# 3b_Motor_Interface.net
KiCad netlist of a schematic drawn in Altium Designer
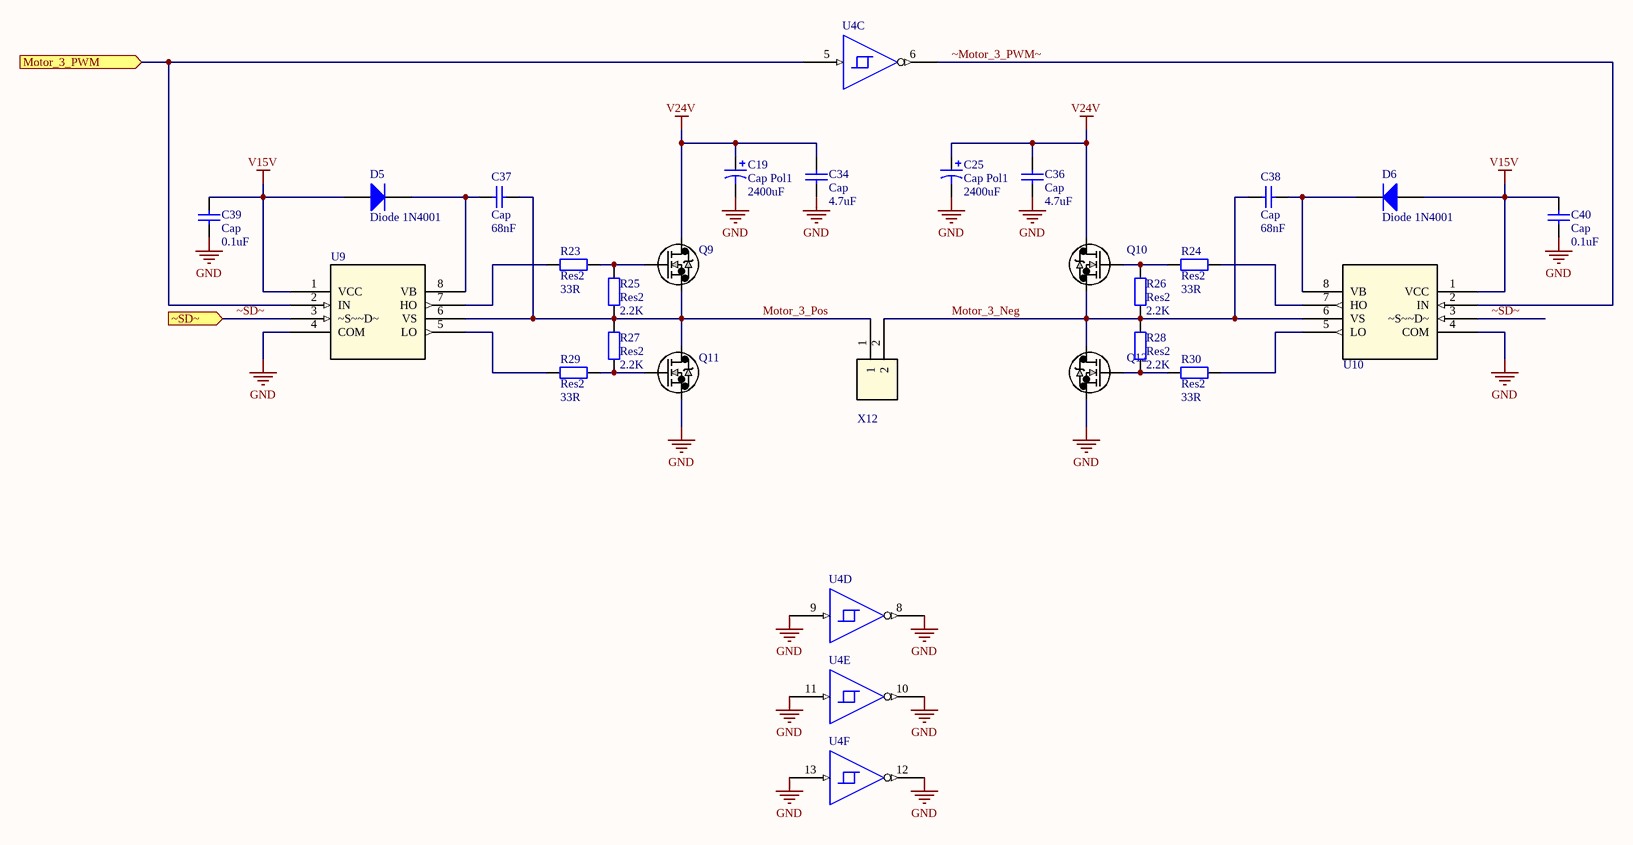
[diagram p0: 3b_Motor_Interface.SchDoc]

(export (version "E")
  (design (tool "Eeschema 10.0.6"))
  (components
    (comp (ref "C19")
      (value "Cap Pol1")
      (footprint "RB7.6-15")
      (description "Polarized Capacitor (Radial)")
      (fields (field (name "ALTIUM_VALUE") "2400uF") (field (name "PUBLISHER") "Altium Limited"))
      (libsource (lib "Miscellaneous Devices") (part "Cap Pol1"))
    )
    (comp (ref "C25")
      (value "Cap Pol1")
      (footprint "RB7.6-15")
      (description "Polarized Capacitor (Radial)")
      (fields (field (name "ALTIUM_VALUE") "2400uF") (field (name "PUBLISHER") "Altium Limited"))
      (libsource (lib "Miscellaneous Devices") (part "Cap Pol1"))
    )
    (comp (ref "C34")
      (value "Cap")
      (footprint "RAD-0.3")
      (description "Capacitor")
      (fields (field (name "ALTIUM_VALUE") "4.7uF") (field (name "PUBLISHER") "Altium Limited"))
      (libsource (lib "Miscellaneous Devices") (part "Cap"))
    )
    (comp (ref "C36")
      (value "Cap")
      (footprint "RAD-0.3")
      (description "Capacitor")
      (fields (field (name "ALTIUM_VALUE") "4.7uF") (field (name "PUBLISHER") "Altium Limited"))
      (libsource (lib "Miscellaneous Devices") (part "Cap"))
    )
    (comp (ref "C37")
      (value "Cap")
      (footprint "RAD-0.3")
      (description "Capacitor")
      (fields (field (name "ALTIUM_VALUE") "68nF") (field (name "PUBLISHER") "Altium Limited"))
      (libsource (lib "Miscellaneous Devices") (part "Cap"))
    )
    (comp (ref "C38")
      (value "Cap")
      (footprint "RAD-0.3")
      (description "Capacitor")
      (fields (field (name "ALTIUM_VALUE") "68nF") (field (name "PUBLISHER") "Altium Limited"))
      (libsource (lib "Miscellaneous Devices") (part "Cap"))
    )
    (comp (ref "C39")
      (value "Cap")
      (footprint "RAD-0.3")
      (description "Capacitor")
      (fields (field (name "ALTIUM_VALUE") "0.1uF") (field (name "PUBLISHER") "Altium Limited"))
      (libsource (lib "Miscellaneous Devices") (part "Cap"))
    )
    (comp (ref "C40")
      (value "Cap")
      (footprint "RAD-0.3")
      (description "Capacitor")
      (fields (field (name "ALTIUM_VALUE") "0.1uF") (field (name "PUBLISHER") "Altium Limited"))
      (libsource (lib "Miscellaneous Devices") (part "Cap"))
    )
    (comp (ref "D5")
      (value "Diode 1N4001")
      (footprint "DO-41")
      (description "1 Amp General Purpose Rectifier")
      (fields (field (name "PUBLISHER") "Altium Limited"))
      (libsource (lib "Miscellaneous Devices") (part "Diode 1N4001"))
    )
    (comp (ref "D6")
      (value "Diode 1N4001")
      (footprint "DO-41")
      (description "1 Amp General Purpose Rectifier")
      (fields (field (name "PUBLISHER") "Altium Limited"))
      (libsource (lib "Miscellaneous Devices") (part "Diode 1N4001"))
    )
    (comp (ref "Q9")
      (value "STP100N6F7")
      (footprint "thomas_lib:TO-220")
      (fields (field (name "DIGI-KEY_PART_NUMBER") "497-15888-5-ND"))
      (libsource (lib "thomas_lib") (part "STP100N6F7"))
    )
    (comp (ref "Q10")
      (value "STP100N6F7")
      (footprint "thomas_lib:TO-220")
      (fields (field (name "DIGI-KEY_PART_NUMBER") "497-15888-5-ND"))
      (libsource (lib "thomas_lib") (part "STP100N6F7"))
    )
    (comp (ref "Q11")
      (value "STP100N6F7")
      (footprint "thomas_lib:TO-220")
      (fields (field (name "DIGI-KEY_PART_NUMBER") "497-15888-5-ND"))
      (libsource (lib "thomas_lib") (part "STP100N6F7"))
    )
    (comp (ref "Q12")
      (value "STP100N6F7")
      (footprint "thomas_lib:TO-220")
      (fields (field (name "DIGI-KEY_PART_NUMBER") "497-15888-5-ND"))
      (libsource (lib "thomas_lib") (part "STP100N6F7"))
    )
    (comp (ref "R23")
      (value "Res2")
      (footprint "AXIAL-0.4")
      (description "Resistor")
      (fields (field (name "ALTIUM_VALUE") "33R") (field (name "PUBLISHER") "Altium Limited"))
      (libsource (lib "Miscellaneous Devices") (part "Res2"))
    )
    (comp (ref "R24")
      (value "Res2")
      (footprint "AXIAL-0.4")
      (description "Resistor")
      (fields (field (name "ALTIUM_VALUE") "33R") (field (name "PUBLISHER") "Altium Limited"))
      (libsource (lib "") (part "Res2_1"))
    )
    (comp (ref "R25")
      (value "Res2")
      (footprint "AXIAL-0.4")
      (description "Resistor")
      (fields (field (name "ALTIUM_VALUE") "2.2K") (field (name "PUBLISHER") "Altium Limited"))
      (libsource (lib "") (part "Res2_2"))
    )
    (comp (ref "R26")
      (value "Res2")
      (footprint "AXIAL-0.4")
      (description "Resistor")
      (fields (field (name "ALTIUM_VALUE") "2.2K") (field (name "PUBLISHER") "Altium Limited"))
      (libsource (lib "Miscellaneous Devices") (part "Res2"))
    )
    (comp (ref "R27")
      (value "Res2")
      (footprint "AXIAL-0.4")
      (description "Resistor")
      (fields (field (name "ALTIUM_VALUE") "2.2K") (field (name "PUBLISHER") "Altium Limited"))
      (libsource (lib "") (part "Res2_2"))
    )
    (comp (ref "R28")
      (value "Res2")
      (footprint "AXIAL-0.4")
      (description "Resistor")
      (fields (field (name "ALTIUM_VALUE") "2.2K") (field (name "PUBLISHER") "Altium Limited"))
      (libsource (lib "Miscellaneous Devices") (part "Res2"))
    )
    (comp (ref "R29")
      (value "Res2")
      (footprint "AXIAL-0.4")
      (description "Resistor")
      (fields (field (name "ALTIUM_VALUE") "33R") (field (name "PUBLISHER") "Altium Limited"))
      (libsource (lib "Miscellaneous Devices") (part "Res2"))
    )
    (comp (ref "R30")
      (value "Res2")
      (footprint "AXIAL-0.4")
      (description "Resistor")
      (fields (field (name "ALTIUM_VALUE") "33R") (field (name "PUBLISHER") "Altium Limited"))
      (libsource (lib "") (part "Res2_1"))
    )
    (comp (ref "U4")
      (value "IC HEX SCHMITT-TRIG INV 14-DIP")
      (footprint "14-DIP")
      (fields
        (field (name "DIGI-KEY_PART_NUMBER") "296-4368-5-ND")
        (field (name "MANUFACTUER_PART_NUMBER") "SN74ACT14N")
        (field (name "MANUFACTURER") "Texas Instruments")
      )
      (libsource (lib "thomas_lib") (part "IC HEX SCHMITT-TRIG INV 14-DIP"))
    )
    (comp (ref "U9")
      (value "IC DRIVER HALF BRIDGE 8DIP")
      (footprint "thomas_lib:8-DIP")
      (fields
        (field (name "MANUFACTURER_PART_NUMBER") "IR2109PBF")
        (field (name "DIGI-KEY_PART_NUMBER") "IR2109PBF-ND")
        (field (name "MANUFACTURER") "Infineon Technologies")
      )
      (libsource (lib "thomas_lib") (part "IC DRIVER HALF BRIDGE 8DIP"))
    )
    (comp (ref "U10")
      (value "IC DRIVER HALF BRIDGE 8DIP")
      (footprint "thomas_lib:8-DIP")
      (fields
        (field (name "MANUFACTURER_PART_NUMBER") "IR2109PBF")
        (field (name "DIGI-KEY_PART_NUMBER") "IR2109PBF-ND")
        (field (name "MANUFACTURER") "Infineon Technologies")
      )
      (libsource (lib "") (part "IC DRIVER HALF BRIDGE 8DIP_1"))
    )
    (comp (ref "X12")
      (value "TERM BLOCK HDR 2POS VERT 3.5MM")
      (footprint "WR-TBL-3211 2")
      (fields
        (field (name "DIGIKEY_PART_NUMBER") "732-2763-ND")
        (field (name "MANUFACTURER_PART_NUMBER") "691321100002")
        (field (name "MANUFACTURER") "Wurth Electronics Inc")
      )
      (libsource (lib "thomas_lib") (part "TERM BLOCK HDR 2POS VERT 3.5MM"))
    )
  )
  (nets
    (net (code "1") (name "/Motor_3_Neg") (class "Default")
      (node (ref "C38") (pin "1") (pinfunction "1_1") (pintype "passive"))
      (node (ref "Q10") (pin "3") (pinfunction "3_3") (pintype "passive"))
      (node (ref "Q12") (pin "2") (pinfunction "2_2") (pintype "passive"))
      (node (ref "R26") (pin "2") (pinfunction "2_2") (pintype "passive"))
      (node (ref "R28") (pin "1") (pinfunction "1_1") (pintype "passive"))
      (node (ref "U10") (pin "6") (pinfunction "VS_6") (pintype "power_in"))
      (node (ref "X12") (pin "2") (pinfunction "2_2") (pintype "passive"))
    )
    (net (code "2") (name "/Motor_3_PWM") (class "Default")
      (node (ref "U4") (pin "5") (pinfunction "A_5") (pintype "input"))
      (node (ref "U9") (pin "2") (pinfunction "IN_2") (pintype "input"))
    )
    (net (code "3") (name "/Motor_3_Pos") (class "Default")
      (node (ref "C37") (pin "1") (pinfunction "1_1") (pintype "passive"))
      (node (ref "Q11") (pin "2") (pinfunction "2_2") (pintype "passive"))
      (node (ref "Q9") (pin "3") (pinfunction "3_3") (pintype "passive"))
      (node (ref "R25") (pin "2") (pinfunction "2_2") (pintype "passive"))
      (node (ref "R27") (pin "1") (pinfunction "1_1") (pintype "passive"))
      (node (ref "U9") (pin "6") (pinfunction "VS_6") (pintype "power_in"))
      (node (ref "X12") (pin "1") (pinfunction "1_1") (pintype "passive"))
    )
    (net (code "4") (name "/~Motor_3_PWM~") (class "Default")
      (node (ref "U10") (pin "2") (pinfunction "IN_2") (pintype "input"))
      (node (ref "U4") (pin "6") (pinfunction "Y_6") (pintype "output"))
    )
    (net (code "5") (name "/~SD~") (class "Default")
      (node (ref "U10") (pin "3") (pinfunction "~S~~D~_3") (pintype "input"))
      (node (ref "U9") (pin "3") (pinfunction "~S~~D~_3") (pintype "input"))
    )
    (net (code "6") (name "GND") (class "Default")
      (node (ref "C19") (pin "2") (pinfunction "2_2") (pintype "passive"))
      (node (ref "C25") (pin "2") (pinfunction "2_2") (pintype "passive"))
      (node (ref "C34") (pin "1") (pinfunction "1_1") (pintype "passive"))
      (node (ref "C36") (pin "1") (pinfunction "1_1") (pintype "passive"))
      (node (ref "C39") (pin "1") (pinfunction "1_1") (pintype "passive"))
      (node (ref "C40") (pin "1") (pinfunction "1_1") (pintype "passive"))
      (node (ref "Q11") (pin "3") (pinfunction "3_3") (pintype "passive"))
      (node (ref "Q12") (pin "3") (pinfunction "3_3") (pintype "passive"))
      (node (ref "U10") (pin "4") (pinfunction "COM_4") (pintype "power_in"))
      (node (ref "U4") (pin "10") (pinfunction "Y_10") (pintype "output"))
      (node (ref "U4") (pin "11") (pinfunction "A_11") (pintype "input"))
      (node (ref "U4") (pin "12") (pinfunction "Y_12") (pintype "output"))
      (node (ref "U4") (pin "13") (pinfunction "A_13") (pintype "input"))
      (node (ref "U4") (pin "8") (pinfunction "Y_8") (pintype "output"))
      (node (ref "U4") (pin "9") (pinfunction "A_9") (pintype "input"))
      (node (ref "U9") (pin "4") (pinfunction "COM_4") (pintype "power_in"))
    )
    (net (code "7") (name "Net-(D5-K)") (class "Default")
      (node (ref "C37") (pin "2") (pinfunction "2_2") (pintype "passive"))
      (node (ref "D5") (pin "2") (pinfunction "K_2") (pintype "passive"))
      (node (ref "U9") (pin "8") (pinfunction "VB_8") (pintype "power_in"))
    )
    (net (code "8") (name "Net-(D6-K)") (class "Default")
      (node (ref "C38") (pin "2") (pinfunction "2_2") (pintype "passive"))
      (node (ref "D6") (pin "2") (pinfunction "K_2") (pintype "passive"))
      (node (ref "U10") (pin "8") (pinfunction "VB_8") (pintype "power_in"))
    )
    (net (code "9") (name "Net-(Q9-Pad1)") (class "Default")
      (node (ref "Q9") (pin "1") (pinfunction "1_1") (pintype "passive"))
      (node (ref "R23") (pin "1") (pinfunction "1_1") (pintype "passive"))
      (node (ref "R25") (pin "1") (pinfunction "1_1") (pintype "passive"))
    )
    (net (code "10") (name "Net-(Q10-Pad1)") (class "Default")
      (node (ref "Q10") (pin "1") (pinfunction "1_1") (pintype "passive"))
      (node (ref "R24") (pin "1") (pinfunction "1_1") (pintype "passive"))
      (node (ref "R26") (pin "1") (pinfunction "1_1") (pintype "passive"))
    )
    (net (code "11") (name "Net-(Q11-Pad1)") (class "Default")
      (node (ref "Q11") (pin "1") (pinfunction "1_1") (pintype "passive"))
      (node (ref "R27") (pin "2") (pinfunction "2_2") (pintype "passive"))
      (node (ref "R29") (pin "1") (pinfunction "1_1") (pintype "passive"))
    )
    (net (code "12") (name "Net-(Q12-Pad1)") (class "Default")
      (node (ref "Q12") (pin "1") (pinfunction "1_1") (pintype "passive"))
      (node (ref "R28") (pin "2") (pinfunction "2_2") (pintype "passive"))
      (node (ref "R30") (pin "1") (pinfunction "1_1") (pintype "passive"))
    )
    (net (code "13") (name "Net-(U9-HO)") (class "Default")
      (node (ref "R23") (pin "2") (pinfunction "2_2") (pintype "passive"))
      (node (ref "U9") (pin "7") (pinfunction "HO_7") (pintype "output"))
    )
    (net (code "14") (name "Net-(U9-LO)") (class "Default")
      (node (ref "R29") (pin "2") (pinfunction "2_2") (pintype "passive"))
      (node (ref "U9") (pin "5") (pinfunction "LO_5") (pintype "output"))
    )
    (net (code "15") (name "Net-(U10-HO)") (class "Default")
      (node (ref "R24") (pin "2") (pinfunction "2_2") (pintype "passive"))
      (node (ref "U10") (pin "7") (pinfunction "HO_7") (pintype "output"))
    )
    (net (code "16") (name "Net-(U10-LO)") (class "Default")
      (node (ref "R30") (pin "2") (pinfunction "2_2") (pintype "passive"))
      (node (ref "U10") (pin "5") (pinfunction "LO_5") (pintype "output"))
    )
    (net (code "17") (name "V15V") (class "Default")
      (node (ref "C39") (pin "2") (pinfunction "2_2") (pintype "passive"))
      (node (ref "C40") (pin "2") (pinfunction "2_2") (pintype "passive"))
      (node (ref "D5") (pin "1") (pinfunction "A_1") (pintype "passive"))
      (node (ref "D6") (pin "1") (pinfunction "A_1") (pintype "passive"))
      (node (ref "U10") (pin "1") (pinfunction "VCC_1") (pintype "power_in"))
      (node (ref "U9") (pin "1") (pinfunction "VCC_1") (pintype "power_in"))
    )
    (net (code "18") (name "V24V") (class "Default")
      (node (ref "C19") (pin "1") (pinfunction "1_1") (pintype "passive"))
      (node (ref "C25") (pin "1") (pinfunction "1_1") (pintype "passive"))
      (node (ref "C34") (pin "2") (pinfunction "2_2") (pintype "passive"))
      (node (ref "C36") (pin "2") (pinfunction "2_2") (pintype "passive"))
      (node (ref "Q10") (pin "2") (pinfunction "2_2") (pintype "passive"))
      (node (ref "Q9") (pin "2") (pinfunction "2_2") (pintype "passive"))
    )
  )
)
